# 0135-dcdc-neg.net
KiCad netlist of a schematic drawn in EAGLE
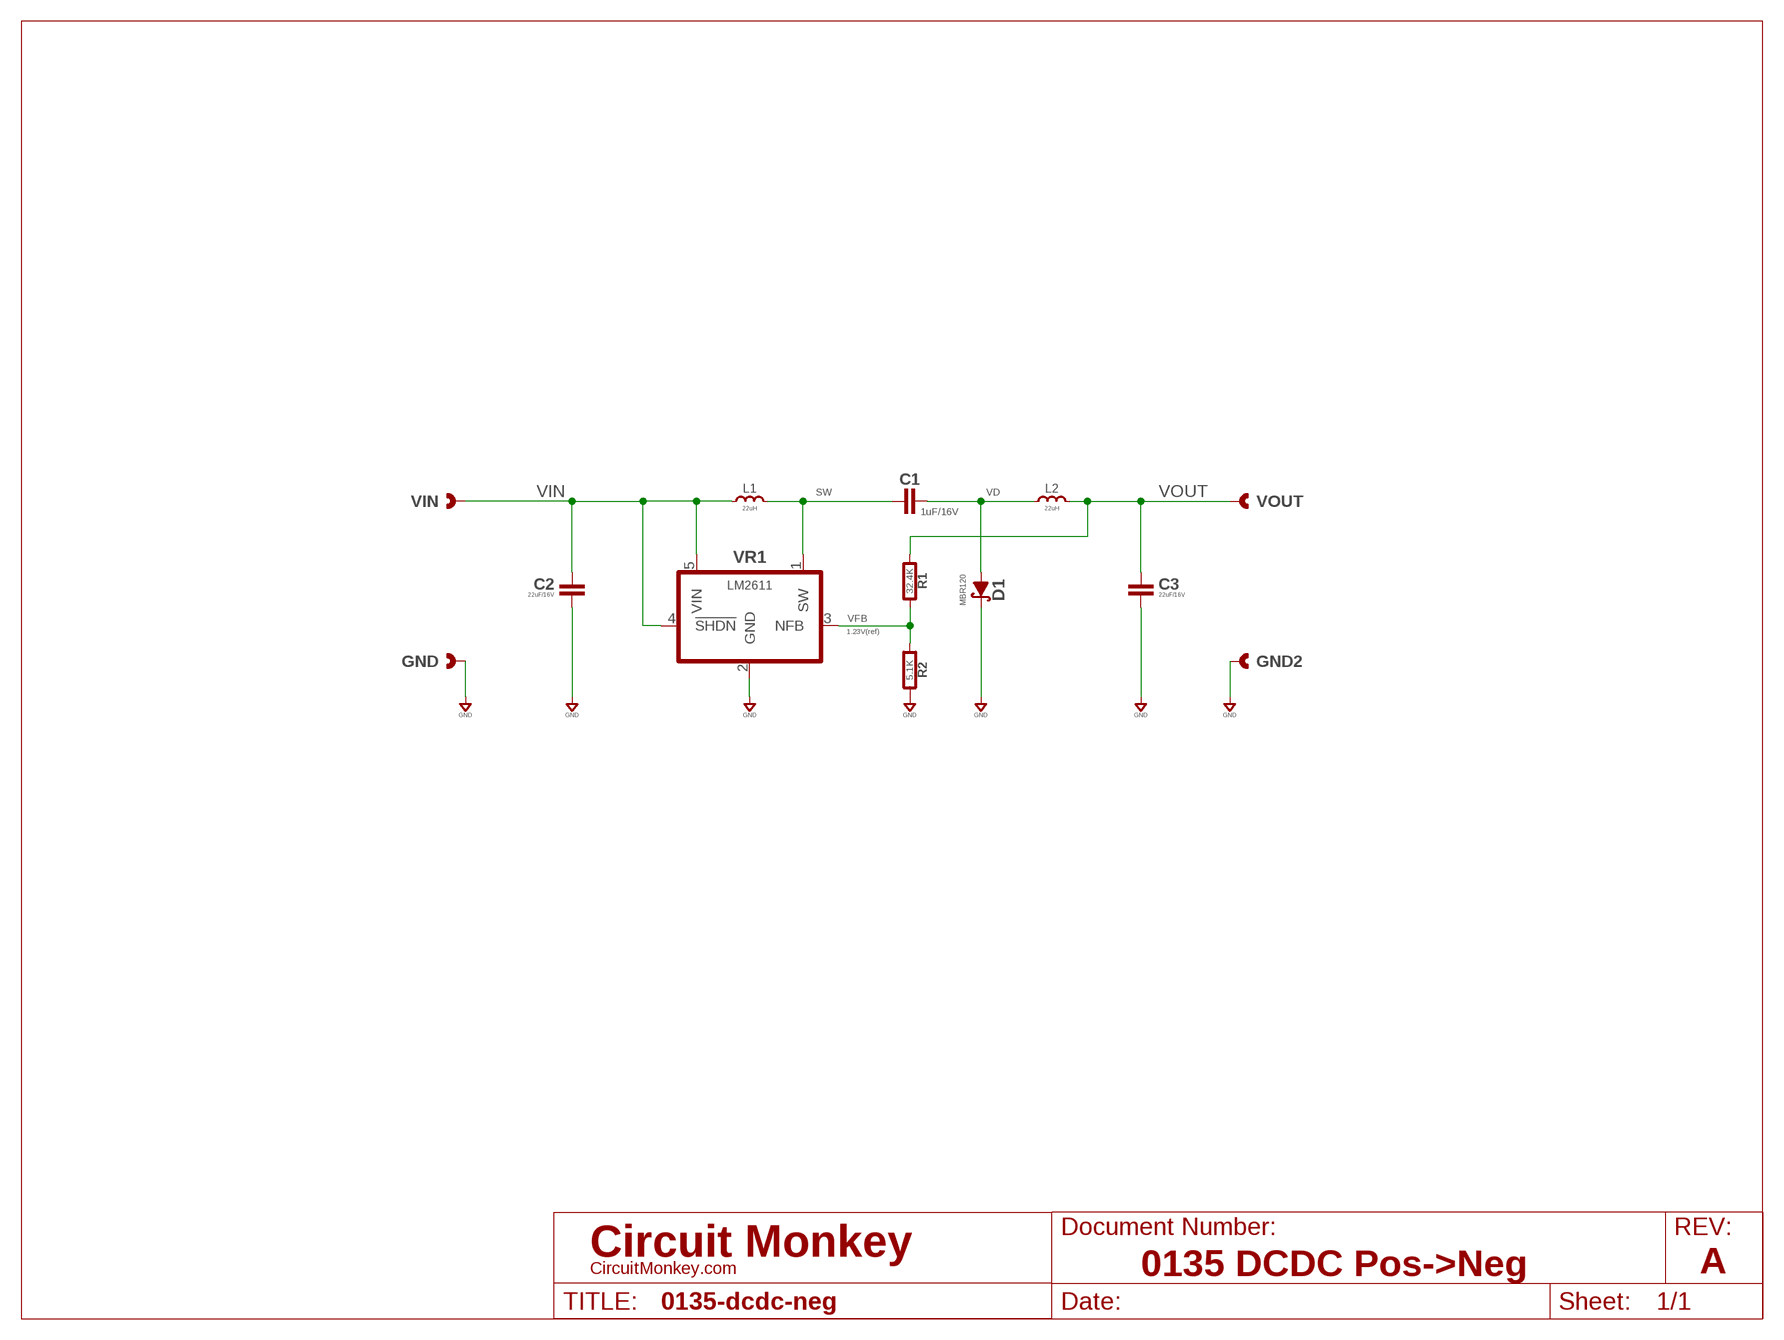
[diagram p0: schematic, sheet 1]

(export (version "E")
  (design (tool "Eeschema 10.0.6"))
  (components
    (comp (ref "C1")
      (value "1uF/16V")
      (footprint "eagle-import:0603-CAP")
      (libsource (lib "eagle-import") (part "CAPACITOR0603"))
    )
    (comp (ref "C2")
      (value "22uF/16V")
      (footprint "eagle-import:1210-CAP")
      (libsource (lib "eagle-import") (part "CAPACITOR1210"))
    )
    (comp (ref "C3")
      (value "22uF/16V")
      (footprint "eagle-import:1210-CAP")
      (libsource (lib "eagle-import") (part "CAPACITOR1210"))
    )
    (comp (ref "D1")
      (value "MBR120")
      (footprint "eagle-import:SOD-123")
      (fields (field (name "MPN") "MBR120ES"))
      (libsource (lib "eagle-import") (part "SCHOTTKYMBR120"))
    )
    (comp (ref "GND")
      (value "CAST-01X12.00MM")
      (footprint "eagle-import:CAST01-2.00MM")
      (libsource (lib "eagle-import") (part "CAST-01X12.00MM"))
    )
    (comp (ref "GND2")
      (value "CAST-01X12.00MM")
      (footprint "eagle-import:CAST01-2.00MM")
      (libsource (lib "eagle-import") (part "CAST-01X12.00MM"))
    )
    (comp (ref "L1")
      (value "22uH")
      (footprint "eagle-import:IND-MU8400")
      (fields (field (name "MFR") "MuRata") (field (name "MPN") "8400 Series"))
      (libsource (lib "eagle-import") (part "INDUCTORSMD-4.5X3.3MM"))
    )
    (comp (ref "L2")
      (value "22uH")
      (footprint "eagle-import:IND-MU8400")
      (fields (field (name "MFR") "MuRata") (field (name "MPN") "8400 Series"))
      (libsource (lib "eagle-import") (part "INDUCTORSMD-4.5X3.3MM"))
    )
    (comp (ref "R1")
      (value "32.4K")
      (footprint "eagle-import:0603-RES")
      (libsource (lib "eagle-import") (part "RESISTOR0603"))
    )
    (comp (ref "R2")
      (value "5.1K")
      (footprint "eagle-import:0603-RES")
      (libsource (lib "eagle-import") (part "RESISTOR0603"))
    )
    (comp (ref "VIN")
      (value "CAST-01X12.00MM")
      (footprint "eagle-import:CAST01-2.00MM")
      (libsource (lib "eagle-import") (part "CAST-01X12.00MM"))
    )
    (comp (ref "VOUT")
      (value "CAST-01X12.00MM")
      (footprint "eagle-import:CAST01-2.00MM")
      (libsource (lib "eagle-import") (part "CAST-01X12.00MM"))
    )
    (comp (ref "VR1")
      (value "LM2611")
      (footprint "eagle-import:SOT-23-5")
      (fields (field (name "MFR") "TI"))
      (libsource (lib "eagle-import") (part "CUK-5P-SOT-23-5"))
    )
  )
  (nets
    (net (code "1") (name "/SW") (class "Default")
      (node (ref "C1") (pin "1") (pinfunction "1_1") (pintype "passive"))
      (node (ref "L1") (pin "1") (pinfunction "P$1_1") (pintype "passive"))
      (node (ref "VR1") (pin "1") (pinfunction "SW_1") (pintype "passive"))
    )
    (net (code "2") (name "/VD") (class "Default")
      (node (ref "C1") (pin "2") (pinfunction "2_2") (pintype "passive"))
      (node (ref "D1") (pin "A") (pinfunction "A_A") (pintype "passive"))
      (node (ref "L2") (pin "2") (pinfunction "P$2_2") (pintype "passive"))
    )
    (net (code "3") (name "/VFB") (class "Default")
      (node (ref "R1") (pin "2") (pinfunction "2_2") (pintype "passive"))
      (node (ref "R2") (pin "1") (pinfunction "1_1") (pintype "passive"))
      (node (ref "VR1") (pin "3") (pinfunction "NFB_3") (pintype "input"))
    )
    (net (code "4") (name "/VIN") (class "Default")
      (node (ref "C2") (pin "1") (pinfunction "1_1") (pintype "passive"))
      (node (ref "L1") (pin "2") (pinfunction "P$2_2") (pintype "passive"))
      (node (ref "VIN") (pin "1") (pinfunction "1_1") (pintype "bidirectional"))
      (node (ref "VIN") (pin "P$1") (pinfunction "1_P$1") (pintype "bidirectional"))
      (node (ref "VIN") (pin "P$2") (pinfunction "1_P$2") (pintype "bidirectional"))
      (node (ref "VR1") (pin "4") (pinfunction "~{SHDN}_4") (pintype "input"))
      (node (ref "VR1") (pin "5") (pinfunction "VIN_5") (pintype "power_in"))
    )
    (net (code "5") (name "/VOUT") (class "Default")
      (node (ref "C3") (pin "1") (pinfunction "1_1") (pintype "passive"))
      (node (ref "L2") (pin "1") (pinfunction "P$1_1") (pintype "passive"))
      (node (ref "R1") (pin "1") (pinfunction "1_1") (pintype "passive"))
      (node (ref "VOUT") (pin "1") (pinfunction "1_1") (pintype "bidirectional"))
      (node (ref "VOUT") (pin "P$1") (pinfunction "1_P$1") (pintype "bidirectional"))
      (node (ref "VOUT") (pin "P$2") (pinfunction "1_P$2") (pintype "bidirectional"))
    )
    (net (code "6") (name "GND") (class "Default")
      (node (ref "C2") (pin "2") (pinfunction "2_2") (pintype "passive"))
      (node (ref "C3") (pin "2") (pinfunction "2_2") (pintype "passive"))
      (node (ref "D1") (pin "K") (pinfunction "K_K") (pintype "passive"))
      (node (ref "GND") (pin "1") (pinfunction "1_1") (pintype "bidirectional"))
      (node (ref "GND") (pin "P$1") (pinfunction "1_P$1") (pintype "bidirectional"))
      (node (ref "GND") (pin "P$2") (pinfunction "1_P$2") (pintype "bidirectional"))
      (node (ref "GND2") (pin "1") (pinfunction "1_1") (pintype "bidirectional"))
      (node (ref "GND2") (pin "P$1") (pinfunction "1_P$1") (pintype "bidirectional"))
      (node (ref "GND2") (pin "P$2") (pinfunction "1_P$2") (pintype "bidirectional"))
      (node (ref "R2") (pin "2") (pinfunction "2_2") (pintype "passive"))
      (node (ref "VR1") (pin "2") (pinfunction "GND_2") (pintype "power_in"))
    )
  )
)
